# Command_Board_Rev_2_4.net
KiCad netlist of a schematic drawn in EAGLE
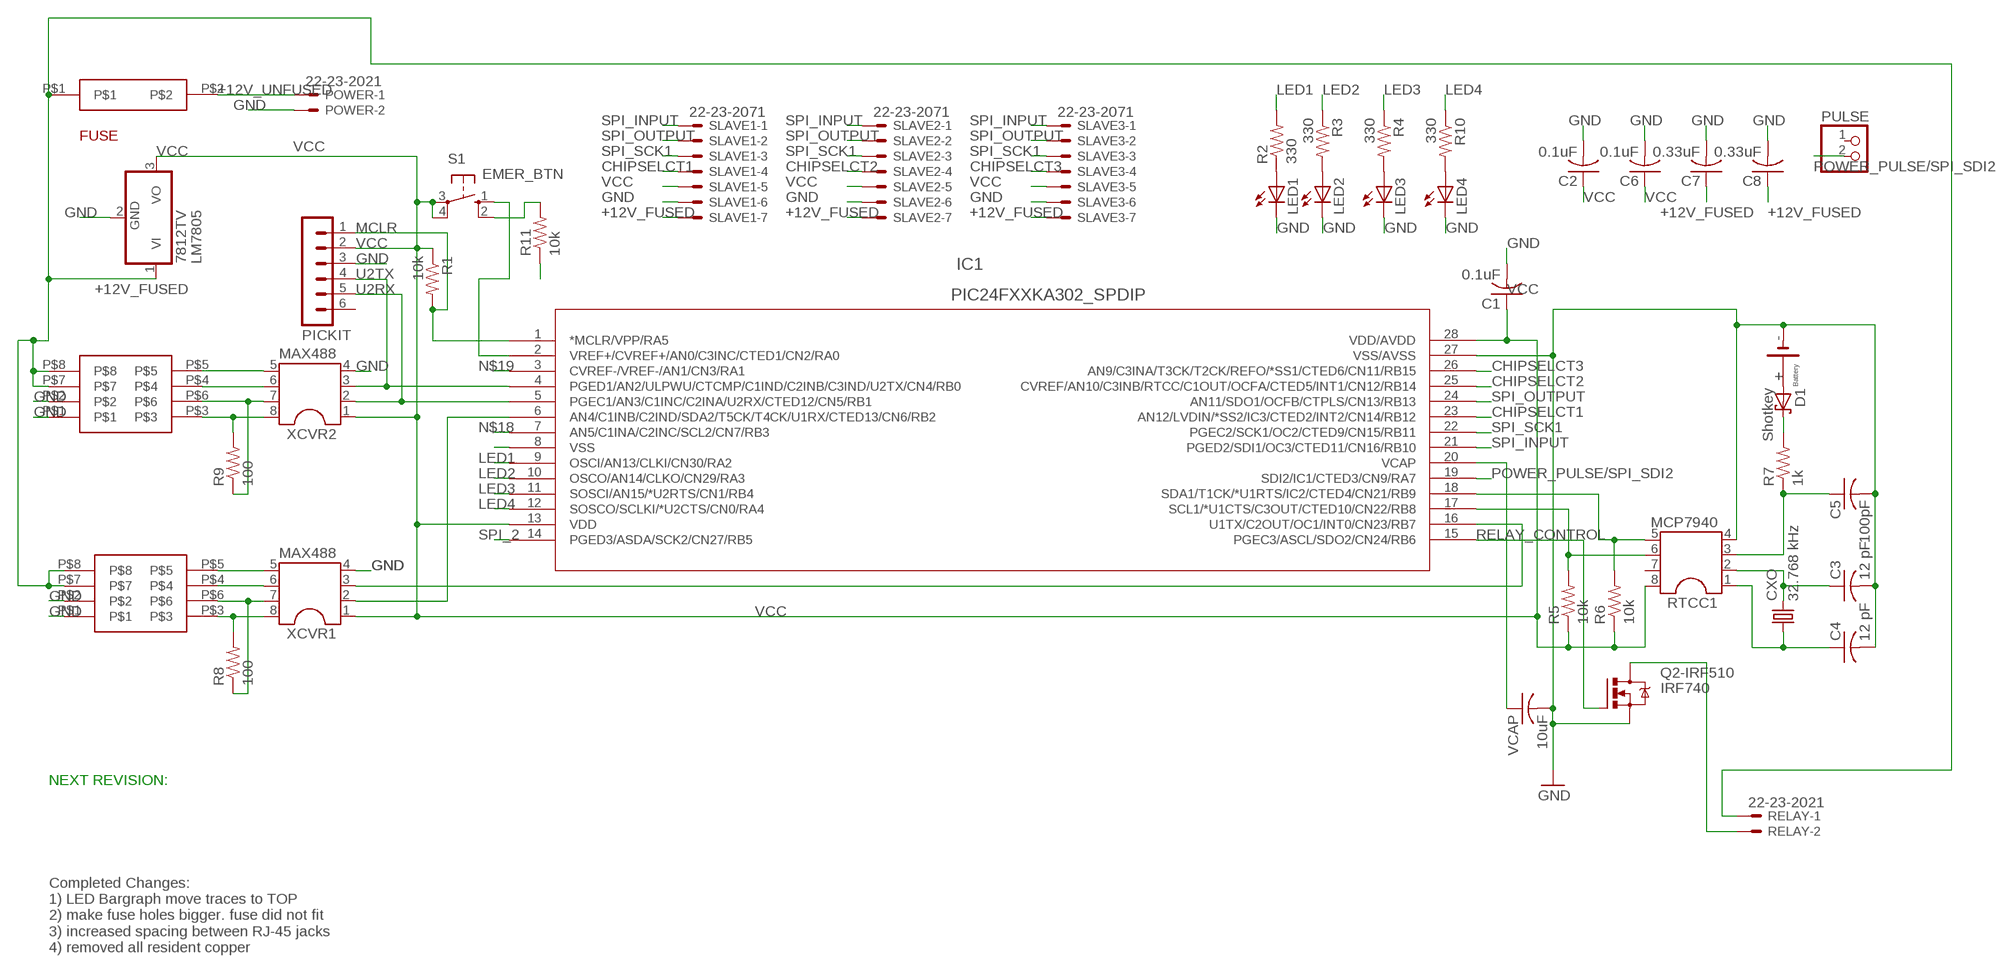
[diagram p0: schematic, sheet 1]

(export (version "E")
  (design (tool "Eeschema 10.0.6"))
  (components
    (comp (ref "BATTERY")
      (value "BATT_S8211R")
      (footprint "eagle-import:BATT_S8211R")
      (libsource (lib "eagle-import") (part "BATT_S8211R"))
    )
    (comp (ref "C1")
      (value "0.1uF")
      (footprint "eagle-import:C025-025X050")
      (libsource (lib "eagle-import") (part "C-US025-025X050"))
    )
    (comp (ref "C2")
      (value "0.1uF")
      (footprint "eagle-import:C025-025X050")
      (libsource (lib "eagle-import") (part "C-US025-025X050"))
    )
    (comp (ref "C3")
      (value "12 pF")
      (footprint "eagle-import:C025-030X050")
      (libsource (lib "eagle-import") (part "resistor_C-US025-030X050"))
    )
    (comp (ref "C4")
      (value "12 pF")
      (footprint "eagle-import:C025-030X050")
      (libsource (lib "eagle-import") (part "resistor_C-US025-030X050"))
    )
    (comp (ref "C5")
      (value "100pF")
      (footprint "eagle-import:C075-042X103")
      (libsource (lib "eagle-import") (part "rcl_C-US075-042X103"))
    )
    (comp (ref "C6")
      (value "0.1uF")
      (footprint "eagle-import:C025-025X050")
      (libsource (lib "eagle-import") (part "C-US025-025X050"))
    )
    (comp (ref "C7")
      (value "0.33uF")
      (footprint "eagle-import:C025-025X050")
      (libsource (lib "eagle-import") (part "C-US025-025X050"))
    )
    (comp (ref "C8")
      (value "0.33uF")
      (footprint "eagle-import:C025-025X050")
      (libsource (lib "eagle-import") (part "C-US025-025X050"))
    )
    (comp (ref "CXO")
      (value "32.768 kHz")
      (footprint "eagle-import:TC26V")
      (libsource (lib "eagle-import") (part "CRYSTALTC26V"))
    )
    (comp (ref "D1")
      (value "Shotkey")
      (footprint "eagle-import:DO41-7.6")
      (libsource (lib "eagle-import") (part "1N5817-B"))
    )
    (comp (ref "F1")
      (value "646_5X20")
      (footprint "eagle-import:646_5X20")
      (libsource (lib "eagle-import") (part "646_5X20"))
    )
    (comp (ref "IC1")
      (value "PIC24FXXKA302_SPDIP")
      (footprint "eagle-import:SPDIP28_300MC")
      (libsource (lib "eagle-import") (part "PIC24FXXKA302_SPDIP"))
    )
    (comp (ref "LED1")
      (value "LED5MM")
      (footprint "eagle-import:LED5MM")
      (libsource (lib "eagle-import") (part "LED5MM"))
    )
    (comp (ref "LED2")
      (value "LED5MM")
      (footprint "eagle-import:LED5MM")
      (libsource (lib "eagle-import") (part "LED5MM"))
    )
    (comp (ref "LED3")
      (value "LED5MM")
      (footprint "eagle-import:LED5MM")
      (libsource (lib "eagle-import") (part "LED5MM"))
    )
    (comp (ref "LED4")
      (value "LED5MM")
      (footprint "eagle-import:LED5MM")
      (libsource (lib "eagle-import") (part "LED5MM"))
    )
    (comp (ref "LM7805")
      (value "7812TV")
      (footprint "eagle-import:TO220V")
      (libsource (lib "eagle-import") (part "78TV12"))
    )
    (comp (ref "PICKIT")
      (value "MA06-1")
      (footprint "eagle-import:MA06-1")
      (libsource (lib "eagle-import") (part "MA06-1"))
    )
    (comp (ref "POWER")
      (value "22-23-2021")
      (footprint "eagle-import:22-23-2021")
      (fields (field (name "MF") "MOLEX"))
      (libsource (lib "eagle-import") (part "22-23-2021"))
    )
    (comp (ref "PULSE")
      (value "PINHD-1X2")
      (footprint "eagle-import:1X02")
      (libsource (lib "eagle-import") (part "PINHD-1X2"))
    )
    (comp (ref "Q2-IRF510")
      (value "IRF740")
      (footprint "eagle-import:TO220BV")
      (libsource (lib "eagle-import") (part "IRF740"))
    )
    (comp (ref "R1")
      (value "10k")
      (footprint "eagle-import:0207_10")
      (libsource (lib "eagle-import") (part "resistor_R-US_0207/10"))
    )
    (comp (ref "R2")
      (value "330")
      (footprint "eagle-import:0207_10")
      (libsource (lib "eagle-import") (part "resistor_R-US_0207/10"))
    )
    (comp (ref "R3")
      (value "330")
      (footprint "eagle-import:0207_10")
      (libsource (lib "eagle-import") (part "resistor_R-US_0207/10"))
    )
    (comp (ref "R4")
      (value "330")
      (footprint "eagle-import:0207_10")
      (libsource (lib "eagle-import") (part "resistor_R-US_0207/10"))
    )
    (comp (ref "R5")
      (value "10k")
      (footprint "eagle-import:0207_10")
      (libsource (lib "eagle-import") (part "resistor_R-US_0207/10"))
    )
    (comp (ref "R6")
      (value "10k")
      (footprint "eagle-import:0207_10")
      (libsource (lib "eagle-import") (part "resistor_R-US_0207/10"))
    )
    (comp (ref "R7")
      (value "1k")
      (footprint "eagle-import:0207_10")
      (libsource (lib "eagle-import") (part "resistor_R-US_0207/10"))
    )
    (comp (ref "R8")
      (value "100")
      (footprint "eagle-import:0309_12")
      (libsource (lib "eagle-import") (part "R-US_0309/12"))
    )
    (comp (ref "R9")
      (value "100")
      (footprint "eagle-import:0309_12")
      (libsource (lib "eagle-import") (part "R-US_0309/12"))
    )
    (comp (ref "R10")
      (value "330")
      (footprint "eagle-import:0207_10")
      (libsource (lib "eagle-import") (part "resistor_R-US_0207/10"))
    )
    (comp (ref "R11")
      (value "10k")
      (footprint "eagle-import:0207_10")
      (libsource (lib "eagle-import") (part "resistor_R-US_0207/10"))
    )
    (comp (ref "RELAY")
      (value "22-23-2021")
      (footprint "eagle-import:22-23-2021")
      (fields (field (name "MF") "MOLEX"))
      (libsource (lib "eagle-import") (part "22-23-2021"))
    )
    (comp (ref "RJ1")
      (value "CAT5")
      (footprint "eagle-import:CAT5")
      (libsource (lib "eagle-import") (part "CAT5"))
    )
    (comp (ref "RJ2")
      (value "CAT5")
      (footprint "eagle-import:CAT5")
      (libsource (lib "eagle-import") (part "CAT5"))
    )
    (comp (ref "RTCC1")
      (value "MCP7940")
      (footprint "eagle-import:DIL08")
      (libsource (lib "eagle-import") (part "DIL8"))
    )
    (comp (ref "S1")
      (value "EMER_BTN")
      (footprint "eagle-import:B3F-40XX")
      (fields (field (name "MF") "OMRON COMPONENTS USA") (field (name "MPN") "B3F-4000"))
      (libsource (lib "eagle-import") (part "40-XX"))
    )
    (comp (ref "SLAVE1")
      (value "22-23-2071")
      (footprint "eagle-import:22-23-2071")
      (fields (field (name "MF") "MOLEX"))
      (libsource (lib "eagle-import") (part "22-23-2071"))
    )
    (comp (ref "SLAVE2")
      (value "22-23-2071")
      (footprint "eagle-import:22-23-2071")
      (fields (field (name "MF") "MOLEX"))
      (libsource (lib "eagle-import") (part "22-23-2071"))
    )
    (comp (ref "SLAVE3")
      (value "22-23-2071")
      (footprint "eagle-import:22-23-2071")
      (fields (field (name "MF") "MOLEX"))
      (libsource (lib "eagle-import") (part "22-23-2071"))
    )
    (comp (ref "VCAP")
      (value "10uF")
      (footprint "eagle-import:C025-050X050")
      (libsource (lib "eagle-import") (part "resistor_C-US025-050X050"))
    )
    (comp (ref "XCVR1")
      (value "MAX488")
      (footprint "eagle-import:DIL08")
      (libsource (lib "eagle-import") (part "DIL8"))
    )
    (comp (ref "XCVR2")
      (value "MAX488")
      (footprint "eagle-import:DIL08")
      (libsource (lib "eagle-import") (part "DIL8"))
    )
  )
  (nets
    (net (code "1") (name "/+12V_FUSED") (class "Default")
      (node (ref "C7") (pin "1") (pinfunction "1_1") (pintype "passive"))
      (node (ref "C8") (pin "1") (pinfunction "1_1") (pintype "passive"))
      (node (ref "F1") (pin "P$1") (pinfunction "P$1_P$1") (pintype "bidirectional"))
      (node (ref "LM7805") (pin "1") (pinfunction "VI_1") (pintype "input"))
      (node (ref "RELAY") (pin "1") (pinfunction "S_1") (pintype "passive"))
      (node (ref "RJ1") (pin "P$7") (pinfunction "P$7_P$7") (pintype "bidirectional"))
      (node (ref "RJ1") (pin "P$8") (pinfunction "P$8_P$8") (pintype "bidirectional"))
      (node (ref "RJ2") (pin "P$7") (pinfunction "P$7_P$7") (pintype "bidirectional"))
      (node (ref "RJ2") (pin "P$8") (pinfunction "P$8_P$8") (pintype "bidirectional"))
      (node (ref "SLAVE1") (pin "7") (pinfunction "S_7") (pintype "passive"))
      (node (ref "SLAVE2") (pin "7") (pinfunction "S_7") (pintype "passive"))
      (node (ref "SLAVE3") (pin "7") (pinfunction "S_7") (pintype "passive"))
    )
    (net (code "2") (name "/+12V_UNFUSED") (class "Default")
      (node (ref "F1") (pin "P$2") (pinfunction "P$2_P$2") (pintype "bidirectional"))
      (node (ref "POWER") (pin "1") (pinfunction "S_1") (pintype "passive"))
    )
    (net (code "3") (name "/CHIPSELCT1") (class "Default")
      (node (ref "IC1") (pin "23") (pinfunction "AN12/LVDIN/*SS2/IC3/CTED2/INT2/CN14/RB12_23") (pintype "passive"))
      (node (ref "SLAVE1") (pin "4") (pinfunction "S_4") (pintype "passive"))
    )
    (net (code "4") (name "/CHIPSELCT2") (class "Default")
      (node (ref "IC1") (pin "25") (pinfunction "CVREF/AN10/C3INB/RTCC/C1OUT/OCFA/CTED5/INT1/CN12/RB14_25") (pintype "passive"))
      (node (ref "SLAVE2") (pin "4") (pinfunction "S_4") (pintype "passive"))
    )
    (net (code "5") (name "/CHIPSELCT3") (class "Default")
      (node (ref "IC1") (pin "26") (pinfunction "AN9/C3INA/T3CK/T2CK/REFO/*SS1/CTED6/CN11/RB15_26") (pintype "passive"))
      (node (ref "SLAVE3") (pin "4") (pinfunction "S_4") (pintype "passive"))
    )
    (net (code "6") (name "/LED1") (class "Default")
      (node (ref "IC1") (pin "9") (pinfunction "OSCI/AN13/CLKI/CN30/RA2_9") (pintype "passive"))
      (node (ref "R2") (pin "2") (pinfunction "2_2") (pintype "passive"))
    )
    (net (code "7") (name "/LED2") (class "Default")
      (node (ref "IC1") (pin "10") (pinfunction "OSCO/AN14/CLKO/CN29/RA3_10") (pintype "passive"))
      (node (ref "R3") (pin "1") (pinfunction "1_1") (pintype "passive"))
    )
    (net (code "8") (name "/LED3") (class "Default")
      (node (ref "IC1") (pin "11") (pinfunction "SOSCI/AN15/*U2RTS/CN1/RB4_11") (pintype "passive"))
      (node (ref "R4") (pin "1") (pinfunction "1_1") (pintype "passive"))
    )
    (net (code "9") (name "/LED4") (class "Default")
      (node (ref "IC1") (pin "12") (pinfunction "SOSCO/SCLKI/*U2CTS/CN0/RA4_12") (pintype "passive"))
      (node (ref "R10") (pin "1") (pinfunction "1_1") (pintype "passive"))
    )
    (net (code "10") (name "/MCLR") (class "Default")
      (node (ref "IC1") (pin "1") (pinfunction "*MCLR/VPP/RA5_1") (pintype "passive"))
      (node (ref "PICKIT") (pin "1") (pinfunction "1_1") (pintype "passive"))
      (node (ref "R1") (pin "2") (pinfunction "2_2") (pintype "passive"))
    )
    (net (code "11") (name "/N$18") (class "Default")
      (node (ref "IC1") (pin "7") (pinfunction "AN5/C1INA/C2INC/SCL2/CN7/RB3_7") (pintype "passive"))
    )
    (net (code "12") (name "/N$19") (class "Default")
      (node (ref "IC1") (pin "3") (pinfunction "CVREF-/VREF-/AN1/CN3/RA1_3") (pintype "passive"))
    )
    (net (code "13") (name "/POWER_PULSE{slash}SPI_SDI2") (class "Default")
      (node (ref "IC1") (pin "19") (pinfunction "SDI2/IC1/CTED3/CN9/RA7_19") (pintype "passive"))
      (node (ref "PULSE") (pin "2") (pinfunction "2_2") (pintype "passive"))
    )
    (net (code "14") (name "/RELAY_CONTROL") (class "Default")
      (node (ref "IC1") (pin "15") (pinfunction "PGEC3/ASCL/SDO2/CN24/RB6_15") (pintype "passive"))
      (node (ref "Q2-IRF510") (pin "G") (pinfunction "G_G") (pintype "passive"))
    )
    (net (code "15") (name "/SPI_2") (class "Default")
      (node (ref "IC1") (pin "14") (pinfunction "PGED3/ASDA/SCK2/CN27/RB5_14") (pintype "passive"))
    )
    (net (code "16") (name "/SPI_INPUT") (class "Default")
      (node (ref "IC1") (pin "21") (pinfunction "PGED2/SDI1/OC3/CTED11/CN16/RB10_21") (pintype "passive"))
      (node (ref "SLAVE1") (pin "1") (pinfunction "S_1") (pintype "passive"))
      (node (ref "SLAVE2") (pin "1") (pinfunction "S_1") (pintype "passive"))
      (node (ref "SLAVE3") (pin "1") (pinfunction "S_1") (pintype "passive"))
    )
    (net (code "17") (name "/SPI_OUTPUT") (class "Default")
      (node (ref "IC1") (pin "24") (pinfunction "AN11/SDO1/OCFB/CTPLS/CN13/RB13_24") (pintype "passive"))
      (node (ref "SLAVE1") (pin "2") (pinfunction "S_2") (pintype "passive"))
      (node (ref "SLAVE2") (pin "2") (pinfunction "S_2") (pintype "passive"))
      (node (ref "SLAVE3") (pin "2") (pinfunction "S_2") (pintype "passive"))
    )
    (net (code "18") (name "/SPI_SCK1") (class "Default")
      (node (ref "IC1") (pin "22") (pinfunction "PGEC2/SCK1/OC2/CTED9/CN15/RB11_22") (pintype "passive"))
      (node (ref "SLAVE1") (pin "3") (pinfunction "S_3") (pintype "passive"))
      (node (ref "SLAVE2") (pin "3") (pinfunction "S_3") (pintype "passive"))
      (node (ref "SLAVE3") (pin "3") (pinfunction "S_3") (pintype "passive"))
    )
    (net (code "19") (name "/U2RX") (class "Default")
      (node (ref "IC1") (pin "5") (pinfunction "PGEC1/AN3/C1INC/C2INA/U2RX/CTED12/CN5/RB1_5") (pintype "passive"))
      (node (ref "PICKIT") (pin "5") (pinfunction "5_5") (pintype "passive"))
      (node (ref "XCVR2") (pin "2") (pinfunction "2_2") (pintype "passive"))
    )
    (net (code "20") (name "/U2TX") (class "Default")
      (node (ref "IC1") (pin "4") (pinfunction "PGED1/AN2/ULPWU/CTCMP/C1IND/C2INB/C3IND/U2TX/CN4/RB0_4") (pintype "passive"))
      (node (ref "PICKIT") (pin "4") (pinfunction "4_4") (pintype "passive"))
      (node (ref "XCVR2") (pin "3") (pinfunction "3_3") (pintype "passive"))
    )
    (net (code "21") (name "/VCC") (class "Default")
      (node (ref "C1") (pin "1") (pinfunction "1_1") (pintype "passive"))
      (node (ref "C2") (pin "1") (pinfunction "1_1") (pintype "passive"))
      (node (ref "C6") (pin "1") (pinfunction "1_1") (pintype "passive"))
      (node (ref "IC1") (pin "13") (pinfunction "VDD_13") (pintype "passive"))
      (node (ref "IC1") (pin "28") (pinfunction "VDD/AVDD_28") (pintype "passive"))
      (node (ref "LM7805") (pin "3") (pinfunction "VO_3") (pintype "passive"))
      (node (ref "PICKIT") (pin "2") (pinfunction "2_2") (pintype "passive"))
      (node (ref "R1") (pin "1") (pinfunction "1_1") (pintype "passive"))
      (node (ref "R5") (pin "1") (pinfunction "1_1") (pintype "passive"))
      (node (ref "R6") (pin "1") (pinfunction "1_1") (pintype "passive"))
      (node (ref "RTCC1") (pin "8") (pinfunction "8_8") (pintype "passive"))
      (node (ref "S1") (pin "3") (pinfunction "P_3") (pintype "passive"))
      (node (ref "S1") (pin "4") (pinfunction "P1_4") (pintype "passive"))
      (node (ref "SLAVE1") (pin "5") (pinfunction "S_5") (pintype "passive"))
      (node (ref "SLAVE2") (pin "5") (pinfunction "S_5") (pintype "passive"))
      (node (ref "SLAVE3") (pin "5") (pinfunction "S_5") (pintype "passive"))
      (node (ref "XCVR1") (pin "1") (pinfunction "1_1") (pintype "passive"))
      (node (ref "XCVR2") (pin "1") (pinfunction "1_1") (pintype "passive"))
    )
    (net (code "22") (name "GND") (class "Default")
      (node (ref "BATTERY") (pin "P-") (pinfunction "-_P-") (pintype "bidirectional"))
      (node (ref "C1") (pin "2") (pinfunction "2_2") (pintype "passive"))
      (node (ref "C2") (pin "2") (pinfunction "2_2") (pintype "passive"))
      (node (ref "C3") (pin "2") (pinfunction "2_2") (pintype "passive"))
      (node (ref "C4") (pin "2") (pinfunction "2_2") (pintype "passive"))
      (node (ref "C5") (pin "2") (pinfunction "2_2") (pintype "passive"))
      (node (ref "C6") (pin "2") (pinfunction "2_2") (pintype "passive"))
      (node (ref "C7") (pin "2") (pinfunction "2_2") (pintype "passive"))
      (node (ref "C8") (pin "2") (pinfunction "2_2") (pintype "passive"))
      (node (ref "IC1") (pin "27") (pinfunction "VSS/AVSS_27") (pintype "passive"))
      (node (ref "IC1") (pin "8") (pinfunction "VSS_8") (pintype "passive"))
      (node (ref "LED1") (pin "K") (pinfunction "C_K") (pintype "passive"))
      (node (ref "LED2") (pin "K") (pinfunction "C_K") (pintype "passive"))
      (node (ref "LED3") (pin "K") (pinfunction "C_K") (pintype "passive"))
      (node (ref "LED4") (pin "K") (pinfunction "C_K") (pintype "passive"))
      (node (ref "LM7805") (pin "2") (pinfunction "GND_2") (pintype "passive"))
      (node (ref "PICKIT") (pin "3") (pinfunction "3_3") (pintype "passive"))
      (node (ref "POWER") (pin "2") (pinfunction "S_2") (pintype "passive"))
      (node (ref "Q2-IRF510") (pin "S") (pinfunction "S_S") (pintype "passive"))
      (node (ref "R11") (pin "1") (pinfunction "1_1") (pintype "passive"))
      (node (ref "RJ1") (pin "P$1") (pinfunction "P$1_P$1") (pintype "bidirectional"))
      (node (ref "RJ1") (pin "P$2") (pinfunction "P$2_P$2") (pintype "bidirectional"))
      (node (ref "RJ2") (pin "P$1") (pinfunction "P$1_P$1") (pintype "bidirectional"))
      (node (ref "RJ2") (pin "P$2") (pinfunction "P$2_P$2") (pintype "bidirectional"))
      (node (ref "RTCC1") (pin "4") (pinfunction "4_4") (pintype "passive"))
      (node (ref "SLAVE1") (pin "6") (pinfunction "S_6") (pintype "passive"))
      (node (ref "SLAVE2") (pin "6") (pinfunction "S_6") (pintype "passive"))
      (node (ref "SLAVE3") (pin "6") (pinfunction "S_6") (pintype "passive"))
      (node (ref "VCAP") (pin "2") (pinfunction "2_2") (pintype "passive"))
      (node (ref "XCVR1") (pin "4") (pinfunction "4_4") (pintype "passive"))
      (node (ref "XCVR2") (pin "4") (pinfunction "4_4") (pintype "passive"))
    )
    (net (code "23") (name "Net-(BATTERY-+-PadP1+)") (class "Default")
      (node (ref "BATTERY") (pin "P1+") (pinfunction "+_P1+") (pintype "bidirectional"))
      (node (ref "BATTERY") (pin "P2+") (pinfunction "+_P2+") (pintype "bidirectional"))
      (node (ref "D1") (pin "A") (pinfunction "A_A") (pintype "passive"))
    )
    (net (code "24") (name "Net-(C3-Pad1)") (class "Default")
      (node (ref "C3") (pin "1") (pinfunction "1_1") (pintype "passive"))
      (node (ref "CXO") (pin "2") (pinfunction "2_2") (pintype "passive"))
      (node (ref "RTCC1") (pin "2") (pinfunction "2_2") (pintype "passive"))
    )
    (net (code "25") (name "Net-(C4-Pad1)") (class "Default")
      (node (ref "C4") (pin "1") (pinfunction "1_1") (pintype "passive"))
      (node (ref "CXO") (pin "1") (pinfunction "1_1") (pintype "passive"))
      (node (ref "RTCC1") (pin "1") (pinfunction "1_1") (pintype "passive"))
    )
    (net (code "26") (name "Net-(C5-Pad1)") (class "Default")
      (node (ref "C5") (pin "1") (pinfunction "1_1") (pintype "passive"))
      (node (ref "R7") (pin "1") (pinfunction "1_1") (pintype "passive"))
      (node (ref "RTCC1") (pin "3") (pinfunction "3_3") (pintype "passive"))
    )
    (net (code "27") (name "Net-(D1-PadC)") (class "Default")
      (node (ref "D1") (pin "C") (pinfunction "C_C") (pintype "passive"))
      (node (ref "R7") (pin "2") (pinfunction "2_2") (pintype "passive"))
    )
    (net (code "28") (name "Net-(IC1-AN4{slash}C1INB{slash}C2IND{slash}SDA2{slash}T5CK{slash}T4CK{slash}U1RX{slash}CTED13{slash}CN6{slash}RB2)") (class "Default")
      (node (ref "IC1") (pin "6") (pinfunction "AN4/C1INB/C2IND/SDA2/T5CK/T4CK/U1RX/CTED13/CN6/RB2_6") (pintype "passive"))
      (node (ref "XCVR1") (pin "2") (pinfunction "2_2") (pintype "passive"))
    )
    (net (code "29") (name "Net-(IC1-SCL1{slash}*U1CTS{slash}C3OUT{slash}CTED10{slash}CN22{slash}RB8)") (class "Default")
      (node (ref "IC1") (pin "17") (pinfunction "SCL1/*U1CTS/C3OUT/CTED10/CN22/RB8_17") (pintype "passive"))
      (node (ref "R5") (pin "2") (pinfunction "2_2") (pintype "passive"))
      (node (ref "RTCC1") (pin "6") (pinfunction "6_6") (pintype "passive"))
    )
    (net (code "30") (name "Net-(IC1-SDA1{slash}T1CK{slash}*U1RTS{slash}IC2{slash}CTED4{slash}CN21{slash}RB9)") (class "Default")
      (node (ref "IC1") (pin "18") (pinfunction "SDA1/T1CK/*U1RTS/IC2/CTED4/CN21/RB9_18") (pintype "passive"))
      (node (ref "R6") (pin "2") (pinfunction "2_2") (pintype "passive"))
      (node (ref "RTCC1") (pin "5") (pinfunction "5_5") (pintype "passive"))
    )
    (net (code "31") (name "Net-(IC1-U1TX{slash}C2OUT{slash}OC1{slash}INT0{slash}CN23{slash}RB7)") (class "Default")
      (node (ref "IC1") (pin "16") (pinfunction "U1TX/C2OUT/OC1/INT0/CN23/RB7_16") (pintype "passive"))
      (node (ref "XCVR1") (pin "3") (pinfunction "3_3") (pintype "passive"))
    )
    (net (code "32") (name "Net-(IC1-VCAP)") (class "Default")
      (node (ref "IC1") (pin "20") (pinfunction "VCAP_20") (pintype "passive"))
      (node (ref "VCAP") (pin "1") (pinfunction "1_1") (pintype "passive"))
    )
    (net (code "33") (name "Net-(IC1-VREF+{slash}CVREF+{slash}AN0{slash}C3INC{slash}CTED1{slash}CN2{slash}RA0)") (class "Default")
      (node (ref "IC1") (pin "2") (pinfunction "VREF+/CVREF+/AN0/C3INC/CTED1/CN2/RA0_2") (pintype "passive"))
      (node (ref "S1") (pin "1") (pinfunction "S_1") (pintype "passive"))
    )
    (net (code "34") (name "Net-(LED1-PadA)") (class "Default")
      (node (ref "LED1") (pin "A") (pinfunction "A_A") (pintype "passive"))
      (node (ref "R2") (pin "1") (pinfunction "1_1") (pintype "passive"))
    )
    (net (code "35") (name "Net-(LED2-PadA)") (class "Default")
      (node (ref "LED2") (pin "A") (pinfunction "A_A") (pintype "passive"))
      (node (ref "R3") (pin "2") (pinfunction "2_2") (pintype "passive"))
    )
    (net (code "36") (name "Net-(LED3-PadA)") (class "Default")
      (node (ref "LED3") (pin "A") (pinfunction "A_A") (pintype "passive"))
      (node (ref "R4") (pin "2") (pinfunction "2_2") (pintype "passive"))
    )
    (net (code "37") (name "Net-(LED4-PadA)") (class "Default")
      (node (ref "LED4") (pin "A") (pinfunction "A_A") (pintype "passive"))
      (node (ref "R10") (pin "2") (pinfunction "2_2") (pintype "passive"))
    )
    (net (code "38") (name "Net-(R8-Pad1)") (class "Default")
      (node (ref "R8") (pin "1") (pinfunction "1_1") (pintype "passive"))
      (node (ref "RJ2") (pin "P$6") (pinfunction "P$6_P$6") (pintype "bidirectional"))
      (node (ref "XCVR1") (pin "7") (pinfunction "7_7") (pintype "passive"))
    )
    (net (code "39") (name "Net-(R8-Pad2)") (class "Default")
      (node (ref "R8") (pin "2") (pinfunction "2_2") (pintype "passive"))
      (node (ref "RJ2") (pin "P$3") (pinfunction "P$3_P$3") (pintype "bidirectional"))
      (node (ref "XCVR1") (pin "8") (pinfunction "8_8") (pintype "passive"))
    )
    (net (code "40") (name "Net-(R9-Pad1)") (class "Default")
      (node (ref "R9") (pin "1") (pinfunction "1_1") (pintype "passive"))
      (node (ref "RJ1") (pin "P$6") (pinfunction "P$6_P$6") (pintype "bidirectional"))
      (node (ref "XCVR2") (pin "7") (pinfunction "7_7") (pintype "passive"))
    )
    (net (code "41") (name "Net-(R9-Pad2)") (class "Default")
      (node (ref "R9") (pin "2") (pinfunction "2_2") (pintype "passive"))
      (node (ref "RJ1") (pin "P$3") (pinfunction "P$3_P$3") (pintype "bidirectional"))
      (node (ref "XCVR2") (pin "8") (pinfunction "8_8") (pintype "passive"))
    )
    (net (code "42") (name "Net-(RELAYB-S)") (class "Default")
      (node (ref "Q2-IRF510") (pin "D") (pinfunction "D_D") (pintype "passive"))
      (node (ref "RELAY") (pin "2") (pinfunction "S_2") (pintype "passive"))
    )
    (net (code "43") (name "Net-(RJ1-PadP$4)") (class "Default")
      (node (ref "RJ1") (pin "P$4") (pinfunction "P$4_P$4") (pintype "bidirectional"))
      (node (ref "XCVR2") (pin "6") (pinfunction "6_6") (pintype "passive"))
    )
    (net (code "44") (name "Net-(RJ1-PadP$5)") (class "Default")
      (node (ref "RJ1") (pin "P$5") (pinfunction "P$5_P$5") (pintype "bidirectional"))
      (node (ref "XCVR2") (pin "5") (pinfunction "5_5") (pintype "passive"))
    )
    (net (code "45") (name "Net-(RJ2-PadP$4)") (class "Default")
      (node (ref "RJ2") (pin "P$4") (pinfunction "P$4_P$4") (pintype "bidirectional"))
      (node (ref "XCVR1") (pin "6") (pinfunction "6_6") (pintype "passive"))
    )
    (net (code "46") (name "Net-(RJ2-PadP$5)") (class "Default")
      (node (ref "RJ2") (pin "P$5") (pinfunction "P$5_P$5") (pintype "bidirectional"))
      (node (ref "XCVR1") (pin "5") (pinfunction "5_5") (pintype "passive"))
    )
    (net (code "47") (name "Net-(S1-S1)") (class "Default")
      (node (ref "R11") (pin "2") (pinfunction "2_2") (pintype "passive"))
      (node (ref "S1") (pin "2") (pinfunction "S1_2") (pintype "passive"))
    )
    (net (code "48") (name "unconnected-(PICKIT-Pad6)") (class "Default")
      (node (ref "PICKIT") (pin "6") (pinfunction "6_6") (pintype "passive"))
    )
    (net (code "49") (name "unconnected-(PULSE-Pad1)") (class "Default")
      (node (ref "PULSE") (pin "1") (pinfunction "1_1") (pintype "passive"))
    )
    (net (code "50") (name "unconnected-(RTCC1-Pad7)") (class "Default")
      (node (ref "RTCC1") (pin "7") (pinfunction "7_7") (pintype "passive"))
    )
  )
)
